# STM32F103.net
KiCad netlist of a schematic drawn in Altium Designer
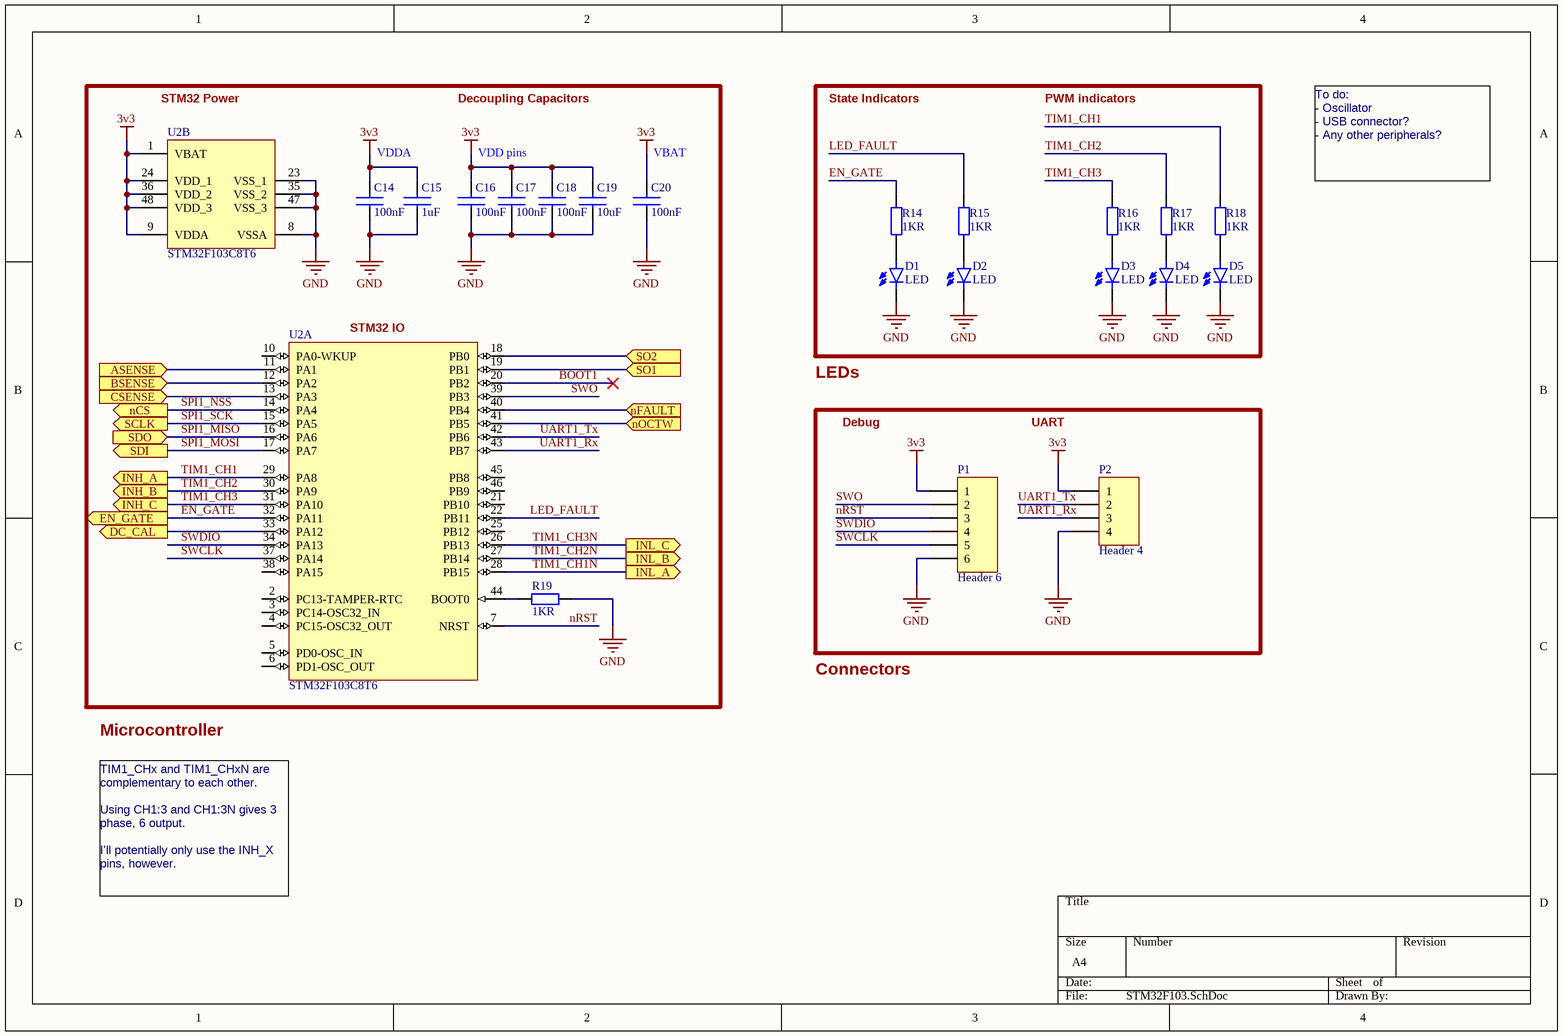
[diagram p0: STM32F103.SchDoc]

(export (version "E")
  (design (tool "Eeschema 10.0.6"))
  (components
    (comp (ref "C14")
      (value "100nF")
      (footprint "RESC0603(1608)_N")
      (description "Non polarized capacitor")
      (libsource (lib "myPassives") (part "Capacitor"))
    )
    (comp (ref "C15")
      (value "1uF")
      (footprint "RESC0603(1608)_N")
      (description "Non polarized capacitor")
      (libsource (lib "myPassives") (part "Capacitor"))
    )
    (comp (ref "C16")
      (value "100nF")
      (footprint "RESC0603(1608)_N")
      (description "Non polarized capacitor")
      (libsource (lib "myPassives") (part "Capacitor"))
    )
    (comp (ref "C17")
      (value "100nF")
      (footprint "RESC0603(1608)_N")
      (description "Non polarized capacitor")
      (libsource (lib "myPassives") (part "Capacitor"))
    )
    (comp (ref "C18")
      (value "100nF")
      (footprint "RESC0603(1608)_N")
      (description "Non polarized capacitor")
      (libsource (lib "myPassives") (part "Capacitor"))
    )
    (comp (ref "C19")
      (value "10uF")
      (footprint "RESC0603(1608)_N")
      (description "Non polarized capacitor")
      (libsource (lib "myPassives") (part "Capacitor"))
    )
    (comp (ref "C20")
      (value "100nF")
      (footprint "RESC0603(1608)_N")
      (description "Non polarized capacitor")
      (libsource (lib "myPassives") (part "Capacitor"))
    )
    (comp (ref "D1") (value "LED") (footprint "0603") (libsource (lib "myPassives") (part "LED")))
    (comp (ref "D2") (value "LED") (footprint "0603") (libsource (lib "myPassives") (part "LED")))
    (comp (ref "D3") (value "LED") (footprint "0603") (libsource (lib "myPassives") (part "LED")))
    (comp (ref "D4") (value "LED") (footprint "0603") (libsource (lib "myPassives") (part "LED")))
    (comp (ref "D5") (value "LED") (footprint "0603") (libsource (lib "myPassives") (part "LED")))
    (comp (ref "P1")
      (value "Header 6")
      (footprint "HDR1X6")
      (description "Header, 6-Pin")
      (fields (field (name "PUBLISHER") "Altium Limited"))
      (libsource (lib "Miscellaneous Connectors") (part "Header 6"))
    )
    (comp (ref "P2")
      (value "Header 4")
      (footprint "HDR1X4")
      (description "Header, 4-Pin")
      (fields (field (name "PUBLISHER") "Altium Limited"))
      (libsource (lib "Miscellaneous Connectors") (part "Header 4"))
    )
    (comp (ref "R14")
      (value "1KR")
      (footprint "RESC0603(1608)_N")
      (description "Resistor")
      (libsource (lib "myPassives") (part "Resistor"))
    )
    (comp (ref "R15")
      (value "1KR")
      (footprint "RESC0603(1608)_N")
      (description "Resistor")
      (libsource (lib "myPassives") (part "Resistor"))
    )
    (comp (ref "R16")
      (value "1KR")
      (footprint "RESC0603(1608)_N")
      (description "Resistor")
      (libsource (lib "myPassives") (part "Resistor"))
    )
    (comp (ref "R17")
      (value "1KR")
      (footprint "RESC0603(1608)_N")
      (description "Resistor")
      (libsource (lib "myPassives") (part "Resistor"))
    )
    (comp (ref "R18")
      (value "1KR")
      (footprint "RESC0603(1608)_N")
      (description "Resistor")
      (libsource (lib "myPassives") (part "Resistor"))
    )
    (comp (ref "R19")
      (value "1KR")
      (footprint "RESC0603(1608)_N")
      (description "Resistor")
      (libsource (lib "") (part "Resistor_1"))
    )
    (comp (ref "U2")
      (value "STM32F103C8T6")
      (footprint "STM-LQFP48_N")
      (libsource (lib "STMicroelectronics STM32 F1") (part "STM32F103C8T6"))
    )
  )
  (nets
    (net (code "1") (name "/ASENSE") (class "Default")
      (node (ref "U2") (pin "11") (pinfunction "PA1_11") (pintype "bidirectional"))
    )
    (net (code "2") (name "/BOOT1") (class "Default")
      (node (ref "U2") (pin "20") (pinfunction "PB2_20") (pintype "bidirectional+no_connect"))
    )
    (net (code "3") (name "/BSENSE") (class "Default")
      (node (ref "U2") (pin "12") (pinfunction "PA2_12") (pintype "bidirectional"))
    )
    (net (code "4") (name "/CSENSE") (class "Default")
      (node (ref "U2") (pin "13") (pinfunction "PA3_13") (pintype "bidirectional"))
    )
    (net (code "5") (name "/DC_CAL") (class "Default")
      (node (ref "U2") (pin "33") (pinfunction "PA12_33") (pintype "bidirectional"))
    )
    (net (code "6") (name "/EN_GATE") (class "Default")
      (node (ref "R14") (pin "1") (pintype "passive"))
      (node (ref "U2") (pin "32") (pinfunction "PA11_32") (pintype "bidirectional"))
    )
    (net (code "7") (name "/LED_FAULT") (class "Default")
      (node (ref "R15") (pin "1") (pintype "passive"))
      (node (ref "U2") (pin "22") (pinfunction "PB11_22") (pintype "bidirectional"))
    )
    (net (code "8") (name "/SO1") (class "Default")
      (node (ref "U2") (pin "19") (pinfunction "PB1_19") (pintype "bidirectional"))
    )
    (net (code "9") (name "/SO2") (class "Default")
      (node (ref "U2") (pin "18") (pinfunction "PB0_18") (pintype "bidirectional"))
    )
    (net (code "10") (name "/SPI1_MISO") (class "Default")
      (node (ref "U2") (pin "16") (pinfunction "PA6_16") (pintype "bidirectional"))
    )
    (net (code "11") (name "/SPI1_MOSI") (class "Default")
      (node (ref "U2") (pin "17") (pinfunction "PA7_17") (pintype "bidirectional"))
    )
    (net (code "12") (name "/SPI1_NSS") (class "Default")
      (node (ref "U2") (pin "14") (pinfunction "PA4_14") (pintype "bidirectional"))
    )
    (net (code "13") (name "/SPI1_SCK") (class "Default")
      (node (ref "U2") (pin "15") (pinfunction "PA5_15") (pintype "bidirectional"))
    )
    (net (code "14") (name "/SWCLK") (class "Default")
      (node (ref "P1") (pin "5") (pinfunction "5_5") (pintype "passive"))
      (node (ref "U2") (pin "37") (pinfunction "PA14_37") (pintype "bidirectional"))
    )
    (net (code "15") (name "/SWDIO") (class "Default")
      (node (ref "P1") (pin "4") (pinfunction "4_4") (pintype "passive"))
      (node (ref "U2") (pin "34") (pinfunction "PA13_34") (pintype "bidirectional"))
    )
    (net (code "16") (name "/SWO") (class "Default")
      (node (ref "P1") (pin "2") (pinfunction "2_2") (pintype "passive"))
      (node (ref "U2") (pin "39") (pinfunction "PB3_39") (pintype "bidirectional"))
    )
    (net (code "17") (name "/TIM1_CH1") (class "Default")
      (node (ref "R18") (pin "1") (pintype "passive"))
      (node (ref "U2") (pin "29") (pinfunction "PA8_29") (pintype "bidirectional"))
    )
    (net (code "18") (name "/TIM1_CH1N") (class "Default")
      (node (ref "U2") (pin "28") (pinfunction "PB15_28") (pintype "bidirectional"))
    )
    (net (code "19") (name "/TIM1_CH2") (class "Default")
      (node (ref "R17") (pin "1") (pintype "passive"))
      (node (ref "U2") (pin "30") (pinfunction "PA9_30") (pintype "bidirectional"))
    )
    (net (code "20") (name "/TIM1_CH2N") (class "Default")
      (node (ref "U2") (pin "27") (pinfunction "PB14_27") (pintype "bidirectional"))
    )
    (net (code "21") (name "/TIM1_CH3") (class "Default")
      (node (ref "R16") (pin "1") (pintype "passive"))
      (node (ref "U2") (pin "31") (pinfunction "PA10_31") (pintype "bidirectional"))
    )
    (net (code "22") (name "/TIM1_CH3N") (class "Default")
      (node (ref "U2") (pin "26") (pinfunction "PB13_26") (pintype "bidirectional"))
    )
    (net (code "23") (name "/UART1_Rx") (class "Default")
      (node (ref "P2") (pin "3") (pinfunction "3_3") (pintype "passive"))
      (node (ref "U2") (pin "43") (pinfunction "PB7_43") (pintype "bidirectional"))
    )
    (net (code "24") (name "/UART1_Tx") (class "Default")
      (node (ref "P2") (pin "2") (pinfunction "2_2") (pintype "passive"))
      (node (ref "U2") (pin "42") (pinfunction "PB6_42") (pintype "bidirectional"))
    )
    (net (code "25") (name "/nFAULT") (class "Default")
      (node (ref "U2") (pin "40") (pinfunction "PB4_40") (pintype "bidirectional"))
    )
    (net (code "26") (name "/nOCTW") (class "Default")
      (node (ref "U2") (pin "41") (pinfunction "PB5_41") (pintype "bidirectional"))
    )
    (net (code "27") (name "/nRST") (class "Default")
      (node (ref "P1") (pin "3") (pinfunction "3_3") (pintype "passive"))
      (node (ref "U2") (pin "7") (pinfunction "NRST_7") (pintype "bidirectional"))
    )
    (net (code "28") (name "3v3") (class "Default")
      (node (ref "C14") (pin "2") (pintype "passive"))
      (node (ref "C15") (pin "2") (pintype "passive"))
      (node (ref "C16") (pin "2") (pintype "passive"))
      (node (ref "C17") (pin "2") (pintype "passive"))
      (node (ref "C18") (pin "2") (pintype "passive"))
      (node (ref "C19") (pin "2") (pintype "passive"))
      (node (ref "C20") (pin "2") (pintype "passive"))
      (node (ref "P1") (pin "1") (pinfunction "1_1") (pintype "passive"))
      (node (ref "P2") (pin "1") (pinfunction "1_1") (pintype "passive"))
      (node (ref "U2") (pin "1") (pinfunction "VBAT_1") (pintype "power_in"))
      (node (ref "U2") (pin "24") (pinfunction "VDD_1_24") (pintype "power_in"))
      (node (ref "U2") (pin "36") (pinfunction "VDD_2_36") (pintype "power_in"))
      (node (ref "U2") (pin "48") (pinfunction "VDD_3_48") (pintype "power_in"))
      (node (ref "U2") (pin "9") (pinfunction "VDDA_9") (pintype "power_in"))
    )
    (net (code "29") (name "GND") (class "Default")
      (node (ref "C14") (pin "1") (pintype "passive"))
      (node (ref "C15") (pin "1") (pintype "passive"))
      (node (ref "C16") (pin "1") (pintype "passive"))
      (node (ref "C17") (pin "1") (pintype "passive"))
      (node (ref "C18") (pin "1") (pintype "passive"))
      (node (ref "C19") (pin "1") (pintype "passive"))
      (node (ref "C20") (pin "1") (pintype "passive"))
      (node (ref "D1") (pin "1") (pintype "passive"))
      (node (ref "D2") (pin "1") (pintype "passive"))
      (node (ref "D3") (pin "1") (pintype "passive"))
      (node (ref "D4") (pin "1") (pintype "passive"))
      (node (ref "D5") (pin "1") (pintype "passive"))
      (node (ref "P1") (pin "6") (pinfunction "6_6") (pintype "passive"))
      (node (ref "P2") (pin "4") (pinfunction "4_4") (pintype "passive"))
      (node (ref "R19") (pin "2") (pintype "passive"))
      (node (ref "U2") (pin "23") (pinfunction "VSS_1_23") (pintype "power_in"))
      (node (ref "U2") (pin "35") (pinfunction "VSS_2_35") (pintype "power_in"))
      (node (ref "U2") (pin "47") (pinfunction "VSS_3_47") (pintype "power_in"))
      (node (ref "U2") (pin "8") (pinfunction "VSSA_8") (pintype "power_in"))
    )
    (net (code "30") (name "Net-(D1-Pad2)") (class "Default")
      (node (ref "D1") (pin "2") (pintype "passive"))
      (node (ref "R14") (pin "2") (pintype "passive"))
    )
    (net (code "31") (name "Net-(D2-Pad2)") (class "Default")
      (node (ref "D2") (pin "2") (pintype "passive"))
      (node (ref "R15") (pin "2") (pintype "passive"))
    )
    (net (code "32") (name "Net-(D3-Pad2)") (class "Default")
      (node (ref "D3") (pin "2") (pintype "passive"))
      (node (ref "R16") (pin "2") (pintype "passive"))
    )
    (net (code "33") (name "Net-(D4-Pad2)") (class "Default")
      (node (ref "D4") (pin "2") (pintype "passive"))
      (node (ref "R17") (pin "2") (pintype "passive"))
    )
    (net (code "34") (name "Net-(D5-Pad2)") (class "Default")
      (node (ref "D5") (pin "2") (pintype "passive"))
      (node (ref "R18") (pin "2") (pintype "passive"))
    )
    (net (code "35") (name "Net-(U2A-BOOT0)") (class "Default")
      (node (ref "R19") (pin "1") (pintype "passive"))
      (node (ref "U2") (pin "44") (pinfunction "BOOT0_44") (pintype "input"))
    )
    (net (code "36") (name "unconnected-(U2A-PA0-WKUP-Pad10)") (class "Default")
      (node (ref "U2") (pin "10") (pinfunction "PA0-WKUP_10") (pintype "bidirectional"))
    )
    (net (code "37") (name "unconnected-(U2A-PA15-Pad38)") (class "Default")
      (node (ref "U2") (pin "38") (pinfunction "PA15_38") (pintype "bidirectional"))
    )
    (net (code "38") (name "unconnected-(U2A-PB8-Pad45)") (class "Default")
      (node (ref "U2") (pin "45") (pinfunction "PB8_45") (pintype "bidirectional"))
    )
    (net (code "39") (name "unconnected-(U2A-PB9-Pad46)") (class "Default")
      (node (ref "U2") (pin "46") (pinfunction "PB9_46") (pintype "bidirectional"))
    )
    (net (code "40") (name "unconnected-(U2A-PB10-Pad21)") (class "Default")
      (node (ref "U2") (pin "21") (pinfunction "PB10_21") (pintype "bidirectional"))
    )
    (net (code "41") (name "unconnected-(U2A-PB12-Pad25)") (class "Default")
      (node (ref "U2") (pin "25") (pinfunction "PB12_25") (pintype "bidirectional"))
    )
    (net (code "42") (name "unconnected-(U2A-PC13-TAMPER-RTC-Pad2)") (class "Default")
      (node (ref "U2") (pin "2") (pinfunction "PC13-TAMPER-RTC_2") (pintype "bidirectional"))
    )
    (net (code "43") (name "unconnected-(U2A-PC14-OSC32_IN-Pad3)") (class "Default")
      (node (ref "U2") (pin "3") (pinfunction "PC14-OSC32_IN_3") (pintype "bidirectional"))
    )
    (net (code "44") (name "unconnected-(U2A-PC15-OSC32_OUT-Pad4)") (class "Default")
      (node (ref "U2") (pin "4") (pinfunction "PC15-OSC32_OUT_4") (pintype "bidirectional"))
    )
    (net (code "45") (name "unconnected-(U2A-PD0-OSC_IN-Pad5)") (class "Default")
      (node (ref "U2") (pin "5") (pinfunction "PD0-OSC_IN_5") (pintype "bidirectional"))
    )
    (net (code "46") (name "unconnected-(U2A-PD1-OSC_OUT-Pad6)") (class "Default")
      (node (ref "U2") (pin "6") (pinfunction "PD1-OSC_OUT_6") (pintype "bidirectional"))
    )
  )
)
